# DWM1000.net
KiCad netlist of a schematic drawn in Altium Designer
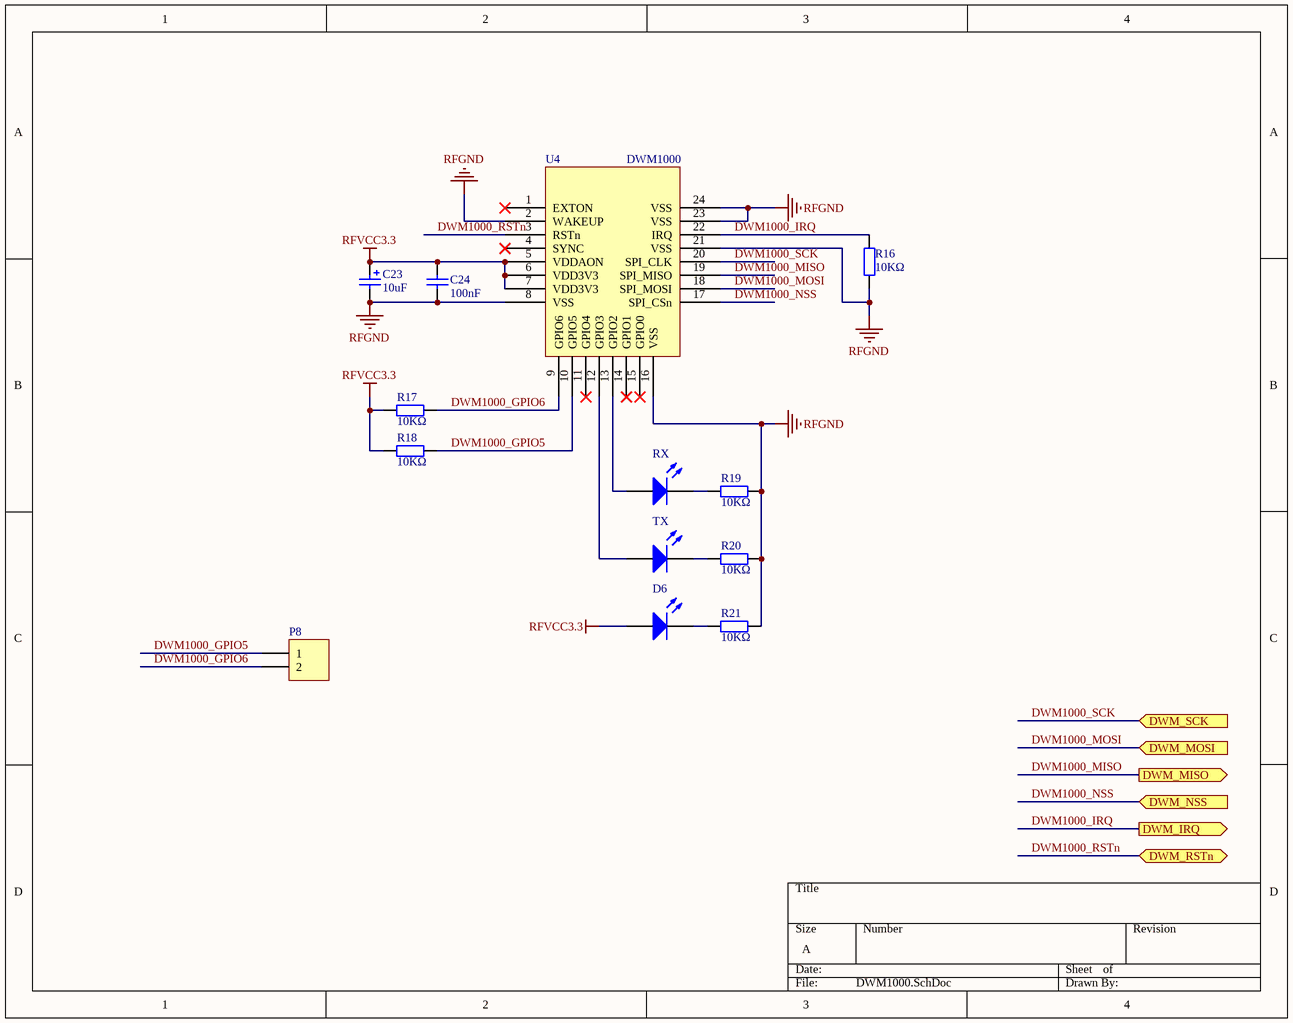
[diagram p0: DWM1000.SchDoc]

(export (version "E")
  (design (tool "Eeschema 10.0.6"))
  (components
    (comp (ref "C23")
      (value "10uF")
      (footprint "CASE-A_3216")
      (description "钽电容")
      (libsource (lib "Miscellaneous Devices LC") (part "3216 10uF (106) 10% 16V"))
    )
    (comp (ref "C24")
      (value "100nF")
      (footprint "0603_C")
      (description "贴片电容")
      (libsource (lib "Miscellaneous Devices LC") (part "0603 100nF (104) 10% 50V"))
    )
    (comp (ref "D6")
      (value "蓝灯 0805")
      (footprint "0805_LED_S1")
      (description "发光二极管")
      (libsource (lib "Miscellaneous Devices LC") (part "0805 蓝灯"))
    )
    (comp (ref "P8")
      (value "Header 2")
      (footprint "HDR1X2")
      (description "Header, 2-Pin")
      (fields (field (name "PUBLISHER") "Altium Limited"))
      (libsource (lib "Miscellaneous Connectors") (part "Header 2"))
    )
    (comp (ref "R16")
      (value "10KΩ")
      (footprint "0603_R")
      (description "贴片电阻")
      (libsource (lib "") (part "0603 10KΩ (1002) 1%_1"))
    )
    (comp (ref "R17")
      (value "10KΩ")
      (footprint "0603_R")
      (description "贴片电阻")
      (libsource (lib "Miscellaneous Devices LC") (part "0603 10KΩ (1002) 1%"))
    )
    (comp (ref "R18")
      (value "10KΩ")
      (footprint "0603_R")
      (description "贴片电阻")
      (libsource (lib "Miscellaneous Devices LC") (part "0603 10KΩ (1002) 1%"))
    )
    (comp (ref "R19")
      (value "10KΩ")
      (footprint "0603_R")
      (description "贴片电阻")
      (libsource (lib "Miscellaneous Devices LC") (part "0603 10KΩ (1002) 1%"))
    )
    (comp (ref "R20")
      (value "10KΩ")
      (footprint "0603_R")
      (description "贴片电阻")
      (libsource (lib "Miscellaneous Devices LC") (part "0603 10KΩ (1002) 1%"))
    )
    (comp (ref "R21")
      (value "10KΩ")
      (footprint "0603_R")
      (description "贴片电阻")
      (libsource (lib "Miscellaneous Devices LC") (part "0603 10KΩ (1002) 1%"))
    )
    (comp (ref "RX")
      (value "蓝灯 0805")
      (footprint "0805_LED_S1")
      (description "发光二极管")
      (libsource (lib "Miscellaneous Devices LC") (part "0805 蓝灯"))
    )
    (comp (ref "TX")
      (value "蓝灯 0805")
      (footprint "0805_LED_S1")
      (description "发光二极管")
      (libsource (lib "Miscellaneous Devices LC") (part "0805 蓝灯"))
    )
    (comp (ref "U4")
      (value "DWM1000")
      (footprint "DWM1000")
      (libsource (lib "DWM1000_pinboard_Project") (part "DWM1000"))
    )
  )
  (nets
    (net (code "1") (name "/DWM1000_GPIO5") (class "Default")
      (node (ref "P8") (pin "1") (pinfunction "1_1") (pintype "passive"))
      (node (ref "R18") (pin "1") (pinfunction "1_1") (pintype "passive"))
      (node (ref "U4") (pin "10") (pinfunction "GPIO5_10") (pintype "passive"))
    )
    (net (code "2") (name "/DWM1000_GPIO6") (class "Default")
      (node (ref "P8") (pin "2") (pinfunction "2_2") (pintype "passive"))
      (node (ref "R17") (pin "1") (pinfunction "1_1") (pintype "passive"))
      (node (ref "U4") (pin "9") (pinfunction "GPIO6_9") (pintype "passive"))
    )
    (net (code "3") (name "/DWM1000_IRQ") (class "Default")
      (node (ref "R16") (pin "2") (pinfunction "2_2") (pintype "passive"))
      (node (ref "U4") (pin "22") (pinfunction "IRQ_22") (pintype "passive"))
    )
    (net (code "4") (name "/DWM1000_MISO") (class "Default")
      (node (ref "U4") (pin "19") (pinfunction "SPI_MISO_19") (pintype "passive"))
    )
    (net (code "5") (name "/DWM1000_MOSI") (class "Default")
      (node (ref "U4") (pin "18") (pinfunction "SPI_MOSI_18") (pintype "passive"))
    )
    (net (code "6") (name "/DWM1000_NSS") (class "Default")
      (node (ref "U4") (pin "17") (pinfunction "SPI_CSn_17") (pintype "passive"))
    )
    (net (code "7") (name "/DWM1000_RSTn") (class "Default")
      (node (ref "U4") (pin "3") (pinfunction "RSTn_3") (pintype "passive"))
    )
    (net (code "8") (name "/DWM1000_SCK") (class "Default")
      (node (ref "U4") (pin "20") (pinfunction "SPI_CLK_20") (pintype "passive"))
    )
    (net (code "9") (name "Net-(D6-PadK)") (class "Default")
      (node (ref "D6") (pin "K") (pinfunction "K_K") (pintype "passive"))
      (node (ref "R21") (pin "2") (pinfunction "2_2") (pintype "passive"))
    )
    (net (code "10") (name "Net-(R19-Pad2)") (class "Default")
      (node (ref "R19") (pin "2") (pinfunction "2_2") (pintype "passive"))
      (node (ref "RX") (pin "K") (pinfunction "K_K") (pintype "passive"))
    )
    (net (code "11") (name "Net-(R20-Pad2)") (class "Default")
      (node (ref "R20") (pin "2") (pinfunction "2_2") (pintype "passive"))
      (node (ref "TX") (pin "K") (pinfunction "K_K") (pintype "passive"))
    )
    (net (code "12") (name "Net-(U4-GPIO2)") (class "Default")
      (node (ref "RX") (pin "A") (pinfunction "A_A") (pintype "passive"))
      (node (ref "U4") (pin "13") (pinfunction "GPIO2_13") (pintype "passive"))
    )
    (net (code "13") (name "Net-(U4-GPIO3)") (class "Default")
      (node (ref "TX") (pin "A") (pinfunction "A_A") (pintype "passive"))
      (node (ref "U4") (pin "12") (pinfunction "GPIO3_12") (pintype "passive"))
    )
    (net (code "14") (name "RFGND") (class "Default")
      (node (ref "C23") (pin "2") (pinfunction "2_2") (pintype "passive"))
      (node (ref "C24") (pin "1") (pinfunction "1_1") (pintype "passive"))
      (node (ref "R16") (pin "1") (pinfunction "1_1") (pintype "passive"))
      (node (ref "R19") (pin "1") (pinfunction "1_1") (pintype "passive"))
      (node (ref "R20") (pin "1") (pinfunction "1_1") (pintype "passive"))
      (node (ref "R21") (pin "1") (pinfunction "1_1") (pintype "passive"))
      (node (ref "U4") (pin "16") (pinfunction "VSS_16") (pintype "passive"))
      (node (ref "U4") (pin "2") (pinfunction "WAKEUP_2") (pintype "passive"))
      (node (ref "U4") (pin "21") (pinfunction "VSS_21") (pintype "passive"))
      (node (ref "U4") (pin "23") (pinfunction "VSS_23") (pintype "passive"))
      (node (ref "U4") (pin "24") (pinfunction "VSS_24") (pintype "passive"))
      (node (ref "U4") (pin "8") (pinfunction "VSS_8") (pintype "passive"))
    )
    (net (code "15") (name "RFVCC3.3") (class "Default")
      (node (ref "C23") (pin "1") (pinfunction "1_1") (pintype "passive"))
      (node (ref "C24") (pin "2") (pinfunction "2_2") (pintype "passive"))
      (node (ref "D6") (pin "A") (pinfunction "A_A") (pintype "passive"))
      (node (ref "R17") (pin "2") (pinfunction "2_2") (pintype "passive"))
      (node (ref "R18") (pin "2") (pinfunction "2_2") (pintype "passive"))
      (node (ref "U4") (pin "5") (pinfunction "VDDAON_5") (pintype "passive"))
      (node (ref "U4") (pin "6") (pinfunction "VDD3V3_6") (pintype "passive"))
      (node (ref "U4") (pin "7") (pinfunction "VDD3V3_7") (pintype "passive"))
    )
    (net (code "16") (name "unconnected-(U4-EXTON-Pad1)") (class "Default")
      (node (ref "U4") (pin "1") (pinfunction "EXTON_1") (pintype "passive+no_connect"))
    )
    (net (code "17") (name "unconnected-(U4-GPIO0-Pad15)") (class "Default")
      (node (ref "U4") (pin "15") (pinfunction "GPIO0_15") (pintype "passive+no_connect"))
    )
    (net (code "18") (name "unconnected-(U4-GPIO1-Pad14)") (class "Default")
      (node (ref "U4") (pin "14") (pinfunction "GPIO1_14") (pintype "passive+no_connect"))
    )
    (net (code "19") (name "unconnected-(U4-GPIO4-Pad11)") (class "Default")
      (node (ref "U4") (pin "11") (pinfunction "GPIO4_11") (pintype "passive+no_connect"))
    )
    (net (code "20") (name "unconnected-(U4-SYNC-Pad4)") (class "Default")
      (node (ref "U4") (pin "4") (pinfunction "SYNC_4") (pintype "passive+no_connect"))
    )
  )
)
